# beagle2can.net
KiCad netlist of a schematic drawn in EAGLE
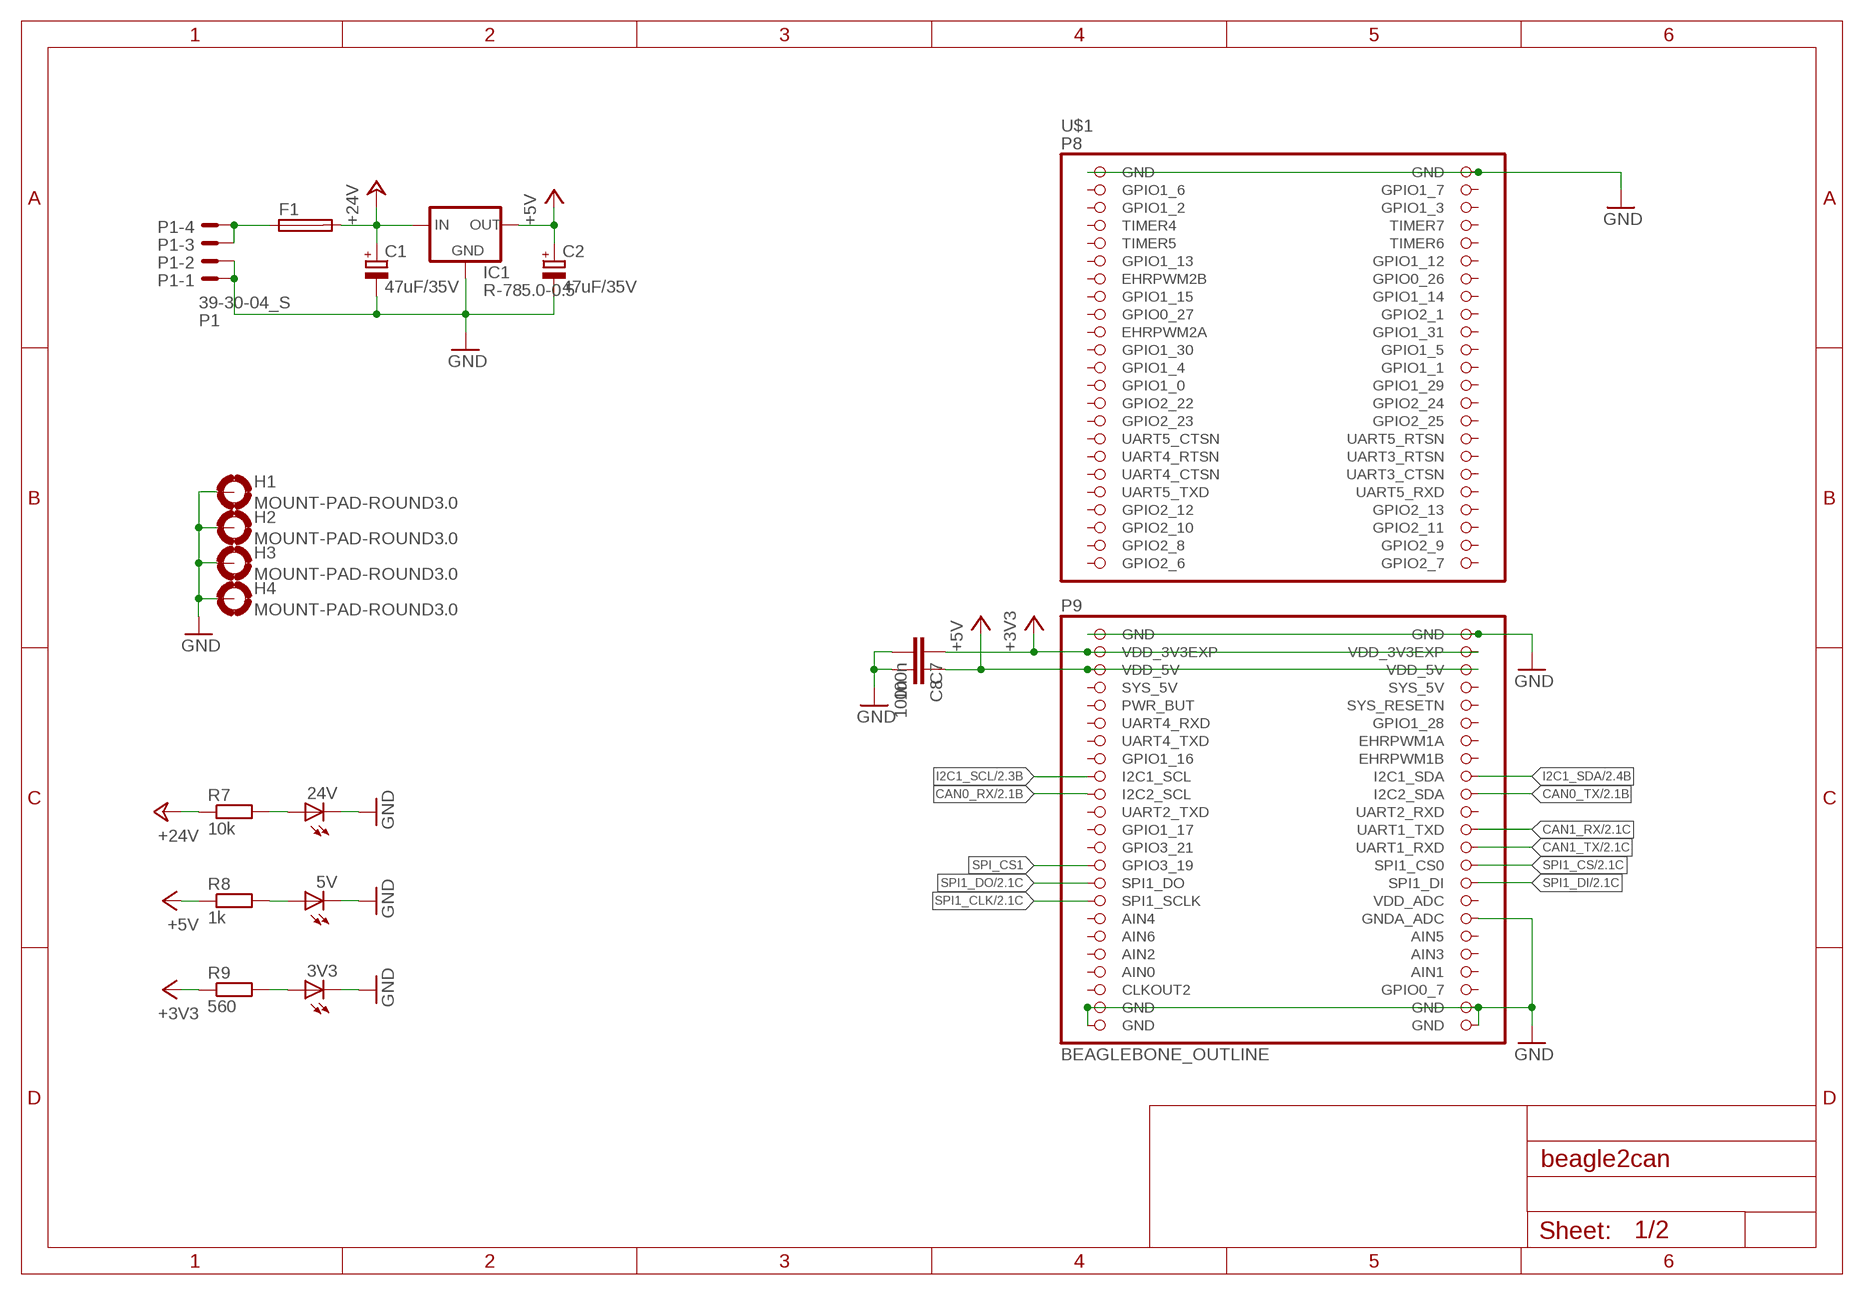
[diagram p0: schematic, sheet 1]
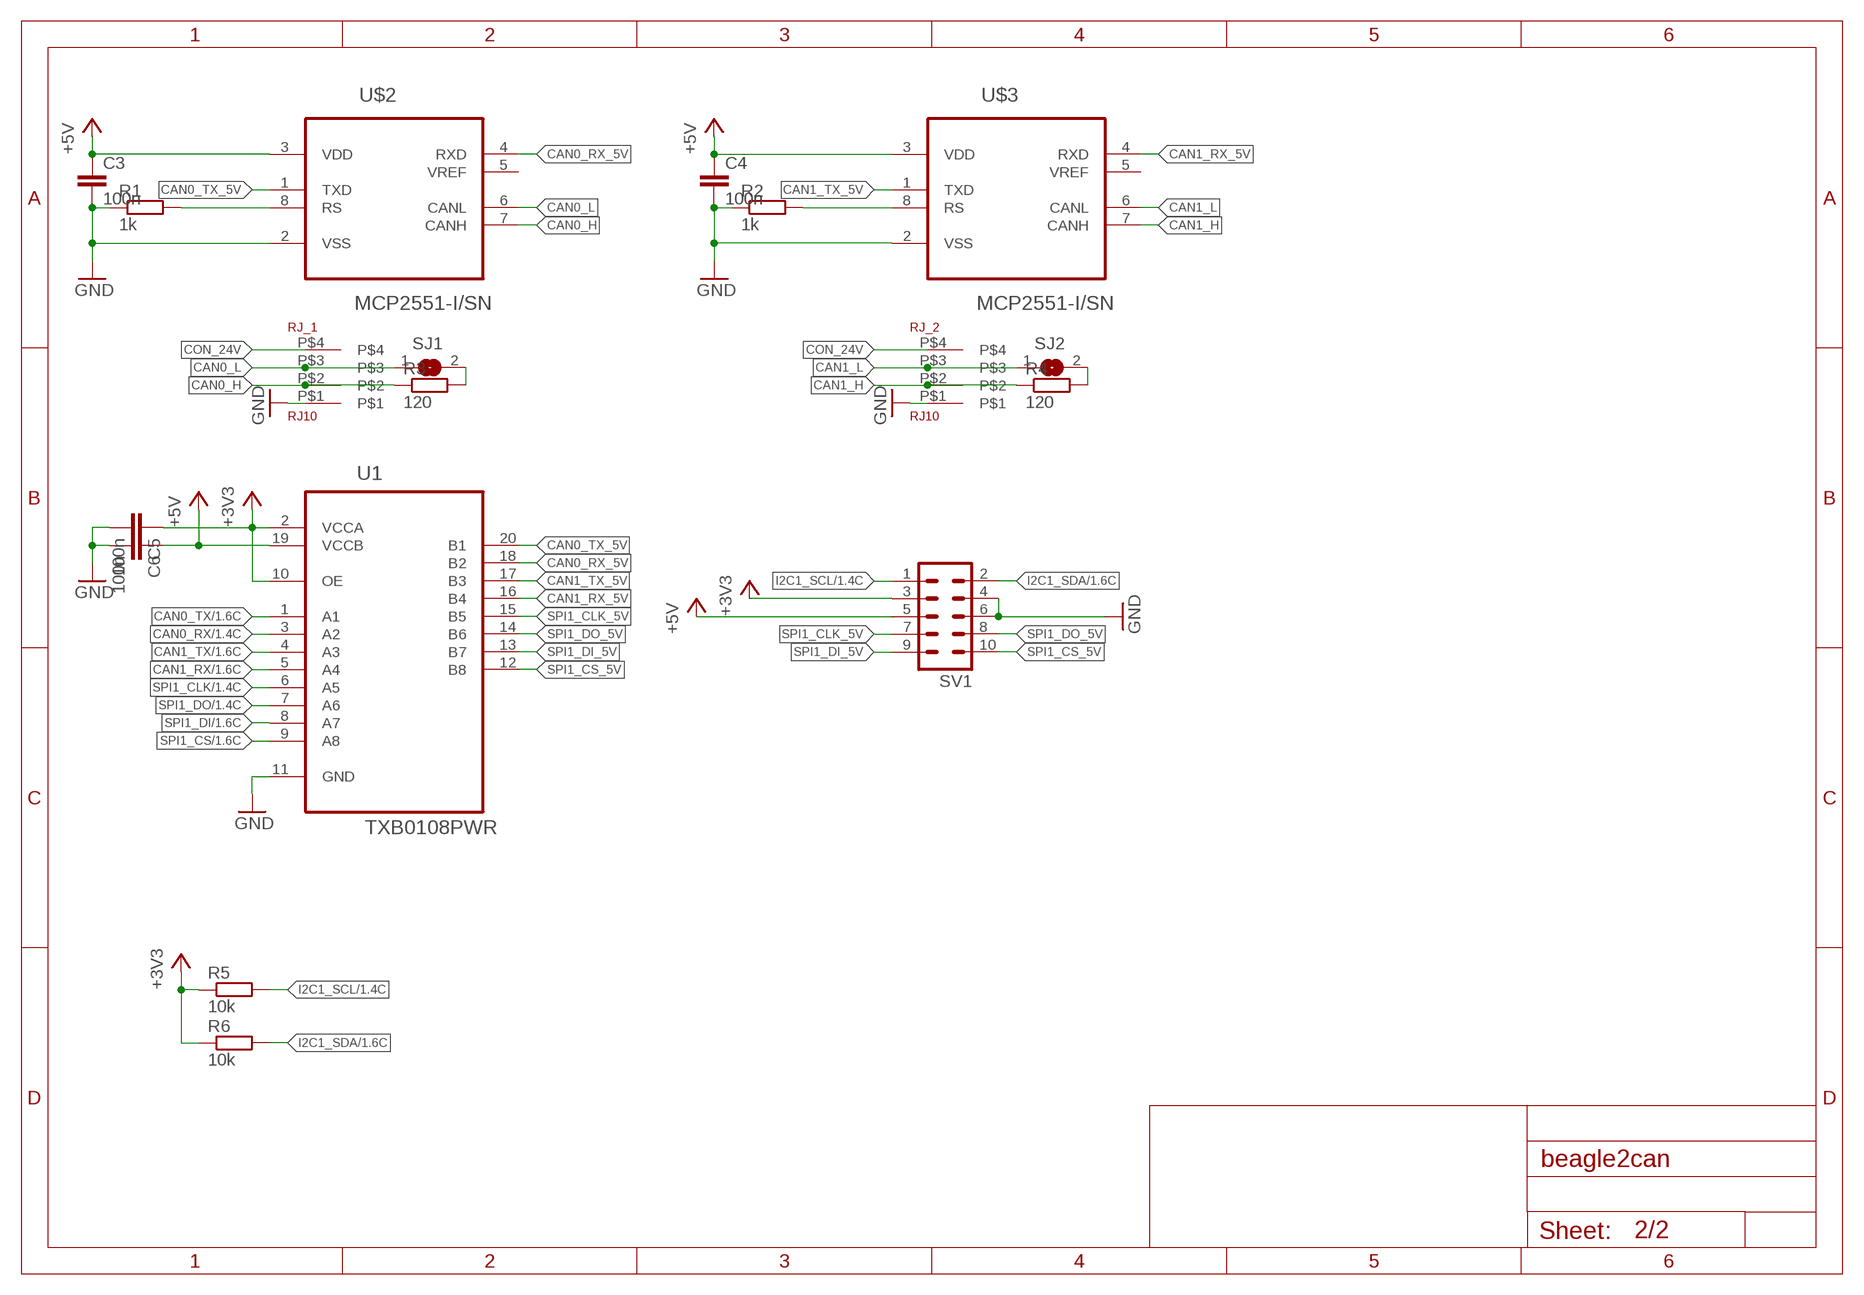
[diagram p1: schematic, sheet 2]

(export (version "E")
  (design (tool "Eeschema 10.0.6"))
  (components
    (comp (ref "C3")
      (value "100n")
      (footprint "eagle-import:C0603")
      (libsource (lib "eagle-import") (part "C-EUC0603"))
    )
    (comp (ref "C4")
      (value "100n")
      (footprint "eagle-import:C0603")
      (libsource (lib "eagle-import") (part "C-EUC0603"))
    )
    (comp (ref "C5")
      (value "100n")
      (footprint "eagle-import:C0603")
      (libsource (lib "eagle-import") (part "C-EUC0603"))
    )
    (comp (ref "C6")
      (value "100n")
      (footprint "eagle-import:C0603")
      (libsource (lib "eagle-import") (part "C-EUC0603"))
    )
    (comp (ref "R1")
      (value "1k")
      (footprint "eagle-import:R0805")
      (libsource (lib "eagle-import") (part "R-EU_R0805"))
    )
    (comp (ref "R2")
      (value "1k")
      (footprint "eagle-import:R0805")
      (libsource (lib "eagle-import") (part "R-EU_R0805"))
    )
    (comp (ref "R3")
      (value "120")
      (footprint "eagle-import:R0805")
      (libsource (lib "eagle-import") (part "R-EU_R0805"))
    )
    (comp (ref "R4")
      (value "120")
      (footprint "eagle-import:R0805")
      (libsource (lib "eagle-import") (part "R-EU_R0805"))
    )
    (comp (ref "R5")
      (value "10k")
      (footprint "eagle-import:R0805")
      (libsource (lib "eagle-import") (part "R-EU_R0805"))
    )
    (comp (ref "R6")
      (value "10k")
      (footprint "eagle-import:R0805")
      (libsource (lib "eagle-import") (part "R-EU_R0805"))
    )
    (comp (ref "RJ_1")
      (value "RJ10")
      (footprint "eagle-import:RJ10")
      (libsource (lib "eagle-import") (part "RJ10"))
    )
    (comp (ref "RJ_2")
      (value "RJ10")
      (footprint "eagle-import:RJ10")
      (libsource (lib "eagle-import") (part "RJ10"))
    )
    (comp (ref "SJ1") (value "SJ") (footprint "eagle-import:SJ") (libsource (lib "eagle-import") (part "SJ")))
    (comp (ref "SJ2") (value "SJ") (footprint "eagle-import:SJ") (libsource (lib "eagle-import") (part "SJ")))
    (comp (ref "SV1")
      (value "ML10L")
      (footprint "eagle-import:ML10L")
      (libsource (lib "eagle-import") (part "ML10L"))
    )
    (comp (ref "U$2")
      (value "MCP2551-I/SN")
      (footprint "eagle-import:SOIC127P600X175-8N")
      (libsource (lib "eagle-import") (part "MCP2551-I/SN"))
    )
    (comp (ref "U$3")
      (value "MCP2551-I/SN")
      (footprint "eagle-import:SOIC127P600X175-8N")
      (libsource (lib "eagle-import") (part "MCP2551-I/SN"))
    )
    (comp (ref "U1")
      (value "TXB0108PWR")
      (footprint "eagle-import:SOP65P640X120-20N")
      (libsource (lib "eagle-import") (part "TXB0108PWR"))
    )
    (comp (ref "3V3")
      (value "LEDCHIP-LED0805")
      (footprint "eagle-import:CHIP-LED0805")
      (libsource (lib "eagle-import") (part "LEDCHIP-LED0805"))
    )
    (comp (ref "5V")
      (value "LEDCHIP-LED0805")
      (footprint "eagle-import:CHIP-LED0805")
      (libsource (lib "eagle-import") (part "LEDCHIP-LED0805"))
    )
    (comp (ref "24V")
      (value "LEDCHIP-LED0805")
      (footprint "eagle-import:CHIP-LED0805")
      (libsource (lib "eagle-import") (part "LEDCHIP-LED0805"))
    )
    (comp (ref "C1")
      (value "47uF/35V")
      (footprint "eagle-import:PANASONIC_D")
      (libsource (lib "eagle-import") (part "CPOL-EUD"))
    )
    (comp (ref "C2")
      (value "47uF/35V")
      (footprint "eagle-import:PANASONIC_D")
      (libsource (lib "eagle-import") (part "CPOL-EUD"))
    )
    (comp (ref "C7")
      (value "100n")
      (footprint "eagle-import:C0603")
      (libsource (lib "eagle-import") (part "C-EUC0603"))
    )
    (comp (ref "C8")
      (value "100n")
      (footprint "eagle-import:C0603")
      (libsource (lib "eagle-import") (part "C-EUC0603"))
    )
    (comp (ref "F1")
      (value "TE5")
      (footprint "eagle-import:TE5")
      (libsource (lib "eagle-import") (part "TE5"))
    )
    (comp (ref "H1")
      (value "MOUNT-PAD-ROUND3.0")
      (footprint "eagle-import:3,0-PAD")
      (libsource (lib "eagle-import") (part "MOUNT-PAD-ROUND3.0"))
    )
    (comp (ref "H2")
      (value "MOUNT-PAD-ROUND3.0")
      (footprint "eagle-import:3,0-PAD")
      (libsource (lib "eagle-import") (part "MOUNT-PAD-ROUND3.0"))
    )
    (comp (ref "H3")
      (value "MOUNT-PAD-ROUND3.0")
      (footprint "eagle-import:3,0-PAD")
      (libsource (lib "eagle-import") (part "MOUNT-PAD-ROUND3.0"))
    )
    (comp (ref "H4")
      (value "MOUNT-PAD-ROUND3.0")
      (footprint "eagle-import:3,0-PAD")
      (libsource (lib "eagle-import") (part "MOUNT-PAD-ROUND3.0"))
    )
    (comp (ref "IC1")
      (value "R-785.0-0.5")
      (footprint "eagle-import:SIP3")
      (fields (field (name "MF") "Recom") (field (name "MPN") "R-785.0-05"))
      (libsource (lib "eagle-import") (part "R-78-0.55.0"))
    )
    (comp (ref "P1")
      (value "39-30-04_S")
      (footprint "eagle-import:39-30-_04_")
      (libsource (lib "eagle-import") (part "39-30-?04?_S"))
    )
    (comp (ref "R7")
      (value "10k")
      (footprint "eagle-import:R0805")
      (libsource (lib "eagle-import") (part "R-EU_R0805"))
    )
    (comp (ref "R8")
      (value "1k")
      (footprint "eagle-import:R0805")
      (libsource (lib "eagle-import") (part "R-EU_R0805"))
    )
    (comp (ref "R9")
      (value "560")
      (footprint "eagle-import:R0805")
      (libsource (lib "eagle-import") (part "R-EU_R0805"))
    )
    (comp (ref "U$1")
      (value "BEAGLEBONE_OUTLINE")
      (footprint "eagle-import:BEAGLEBONE_SHIELD")
      (libsource (lib "eagle-import") (part "BEAGLEBONE_OUTLINE"))
    )
  )
  (nets
    (net (code "1") (name "+3V3") (class "Default")
      (node (ref "C5") (pin "1") (pinfunction "1_1") (pintype "passive"))
      (node (ref "C7") (pin "1") (pinfunction "1_1") (pintype "passive"))
      (node (ref "R5") (pin "1") (pinfunction "1_1") (pintype "passive"))
      (node (ref "R6") (pin "1") (pinfunction "1_1") (pintype "passive"))
      (node (ref "R9") (pin "1") (pinfunction "1_1") (pintype "passive"))
      (node (ref "SV1") (pin "3") (pinfunction "3_3") (pintype "passive"))
      (node (ref "U$1") (pin "49") (pinfunction "VDD_3V3EXP_49") (pintype "power_in"))
      (node (ref "U$1") (pin "50") (pinfunction "VDD_3V3EXP_50") (pintype "power_in"))
      (node (ref "U1") (pin "10") (pinfunction "OE_10") (pintype "input"))
      (node (ref "U1") (pin "2") (pinfunction "VCCA_2") (pintype "power_in"))
    )
    (net (code "2") (name "+5V") (class "Default")
      (node (ref "C2") (pin "+") (pinfunction "+_+") (pintype "passive"))
      (node (ref "C3") (pin "1") (pinfunction "1_1") (pintype "passive"))
      (node (ref "C4") (pin "1") (pinfunction "1_1") (pintype "passive"))
      (node (ref "C6") (pin "1") (pinfunction "1_1") (pintype "passive"))
      (node (ref "C8") (pin "1") (pinfunction "1_1") (pintype "passive"))
      (node (ref "IC1") (pin "3") (pinfunction "OUT_3") (pintype "passive"))
      (node (ref "R8") (pin "1") (pinfunction "1_1") (pintype "passive"))
      (node (ref "SV1") (pin "5") (pinfunction "5_5") (pintype "passive"))
      (node (ref "U$1") (pin "51") (pinfunction "VDD_5V_51") (pintype "power_in"))
      (node (ref "U$1") (pin "52") (pinfunction "VDD_5V_52") (pintype "power_in"))
      (node (ref "U$2") (pin "3") (pinfunction "VDD_3") (pintype "power_in"))
      (node (ref "U$3") (pin "3") (pinfunction "VDD_3") (pintype "power_in"))
      (node (ref "U1") (pin "19") (pinfunction "VCCB_19") (pintype "power_in"))
    )
    (net (code "3") (name "+24V") (class "Default")
      (node (ref "C1") (pin "+") (pinfunction "+_+") (pintype "passive"))
      (node (ref "F1") (pin "2") (pinfunction "2_2") (pintype "passive"))
      (node (ref "IC1") (pin "1") (pinfunction "IN_1") (pintype "input"))
      (node (ref "R7") (pin "1") (pinfunction "1_1") (pintype "passive"))
    )
    (net (code "4") (name "AIN0") (class "Default")
      (node (ref "U$1") (pin "85") (pinfunction "AIN0_85") (pintype "power_in"))
    )
    (net (code "5") (name "CAN0_H") (class "Default")
      (node (ref "R3") (pin "1") (pinfunction "1_1") (pintype "passive"))
      (node (ref "RJ_1") (pin "P$2") (pinfunction "P$2_P$2") (pintype "bidirectional"))
      (node (ref "U$2") (pin "7") (pinfunction "CANH_7") (pintype "bidirectional"))
    )
    (net (code "6") (name "CAN0_L") (class "Default")
      (node (ref "RJ_1") (pin "P$3") (pinfunction "P$3_P$3") (pintype "bidirectional"))
      (node (ref "SJ1") (pin "1") (pinfunction "1_1") (pintype "passive"))
      (node (ref "U$2") (pin "6") (pinfunction "CANL_6") (pintype "bidirectional"))
    )
    (net (code "7") (name "CAN0_RX") (class "Default")
      (node (ref "U$1") (pin "65") (pinfunction "I2C2_SCL_65") (pintype "passive"))
      (node (ref "U1") (pin "3") (pinfunction "A2_3") (pintype "bidirectional"))
    )
    (net (code "8") (name "CAN0_RX_5V") (class "Default")
      (node (ref "U$2") (pin "4") (pinfunction "RXD_4") (pintype "output"))
      (node (ref "U1") (pin "18") (pinfunction "B2_18") (pintype "bidirectional"))
    )
    (net (code "9") (name "CAN0_TX") (class "Default")
      (node (ref "U$1") (pin "66") (pinfunction "I2C2_SDA_66") (pintype "passive"))
      (node (ref "U1") (pin "1") (pinfunction "A1_1") (pintype "bidirectional"))
    )
    (net (code "10") (name "CAN0_TX_5V") (class "Default")
      (node (ref "U$2") (pin "1") (pinfunction "TXD_1") (pintype "input"))
      (node (ref "U1") (pin "20") (pinfunction "B1_20") (pintype "bidirectional"))
    )
    (net (code "11") (name "CAN1_H") (class "Default")
      (node (ref "R4") (pin "1") (pinfunction "1_1") (pintype "passive"))
      (node (ref "RJ_2") (pin "P$2") (pinfunction "P$2_P$2") (pintype "bidirectional"))
      (node (ref "U$3") (pin "7") (pinfunction "CANH_7") (pintype "bidirectional"))
    )
    (net (code "12") (name "CAN1_L") (class "Default")
      (node (ref "RJ_2") (pin "P$3") (pinfunction "P$3_P$3") (pintype "bidirectional"))
      (node (ref "SJ2") (pin "1") (pinfunction "1_1") (pintype "passive"))
      (node (ref "U$3") (pin "6") (pinfunction "CANL_6") (pintype "bidirectional"))
    )
    (net (code "13") (name "CAN1_RX") (class "Default")
      (node (ref "U$1") (pin "70") (pinfunction "UART1_TXD_70") (pintype "passive"))
      (node (ref "U1") (pin "5") (pinfunction "A4_5") (pintype "bidirectional"))
    )
    (net (code "14") (name "CAN1_RX_5V") (class "Default")
      (node (ref "U$3") (pin "4") (pinfunction "RXD_4") (pintype "output"))
      (node (ref "U1") (pin "16") (pinfunction "B4_16") (pintype "bidirectional"))
    )
    (net (code "15") (name "CAN1_TX") (class "Default")
      (node (ref "U$1") (pin "72") (pinfunction "UART1_RXD_72") (pintype "passive"))
      (node (ref "U1") (pin "4") (pinfunction "A3_4") (pintype "bidirectional"))
    )
    (net (code "16") (name "CAN1_TX_5V") (class "Default")
      (node (ref "U$3") (pin "1") (pinfunction "TXD_1") (pintype "input"))
      (node (ref "U1") (pin "17") (pinfunction "B3_17") (pintype "bidirectional"))
    )
    (net (code "17") (name "CON_24V") (class "Default")
      (node (ref "F1") (pin "1") (pinfunction "1_1") (pintype "passive"))
      (node (ref "P1") (pin "3") (pinfunction "P_3") (pintype "passive"))
      (node (ref "P1") (pin "4") (pinfunction "P_4") (pintype "passive"))
      (node (ref "RJ_1") (pin "P$4") (pinfunction "P$4_P$4") (pintype "bidirectional"))
      (node (ref "RJ_2") (pin "P$4") (pinfunction "P$4_P$4") (pintype "bidirectional"))
    )
    (net (code "18") (name "GND") (class "Default")
      (node (ref "24V") (pin "C") (pinfunction "C_C") (pintype "passive"))
      (node (ref "3V3") (pin "C") (pinfunction "C_C") (pintype "passive"))
      (node (ref "5V") (pin "C") (pinfunction "C_C") (pintype "passive"))
      (node (ref "C1") (pin "-") (pinfunction "-_-") (pintype "passive"))
      (node (ref "C2") (pin "-") (pinfunction "-_-") (pintype "passive"))
      (node (ref "C3") (pin "2") (pinfunction "2_2") (pintype "passive"))
      (node (ref "C4") (pin "2") (pinfunction "2_2") (pintype "passive"))
      (node (ref "C5") (pin "2") (pinfunction "2_2") (pintype "passive"))
      (node (ref "C6") (pin "2") (pinfunction "2_2") (pintype "passive"))
      (node (ref "C7") (pin "2") (pinfunction "2_2") (pintype "passive"))
      (node (ref "C8") (pin "2") (pinfunction "2_2") (pintype "passive"))
      (node (ref "H1") (pin "B3,0") (pinfunction "MOUNT_B3,0") (pintype "passive"))
      (node (ref "H2") (pin "B3,0") (pinfunction "MOUNT_B3,0") (pintype "passive"))
      (node (ref "H3") (pin "B3,0") (pinfunction "MOUNT_B3,0") (pintype "passive"))
      (node (ref "H4") (pin "B3,0") (pinfunction "MOUNT_B3,0") (pintype "passive"))
      (node (ref "IC1") (pin "2") (pinfunction "GND_2") (pintype "input"))
      (node (ref "P1") (pin "1") (pinfunction "P_1") (pintype "passive"))
      (node (ref "P1") (pin "2") (pinfunction "P_2") (pintype "passive"))
      (node (ref "R1") (pin "1") (pinfunction "1_1") (pintype "passive"))
      (node (ref "R2") (pin "1") (pinfunction "1_1") (pintype "passive"))
      (node (ref "RJ_1") (pin "P$1") (pinfunction "P$1_P$1") (pintype "bidirectional"))
      (node (ref "RJ_2") (pin "P$1") (pinfunction "P$1_P$1") (pintype "bidirectional"))
      (node (ref "SV1") (pin "4") (pinfunction "4_4") (pintype "passive"))
      (node (ref "SV1") (pin "6") (pinfunction "6_6") (pintype "passive"))
      (node (ref "U$1") (pin "1") (pinfunction "GND_1") (pintype "power_in"))
      (node (ref "U$1") (pin "2") (pinfunction "GND_2") (pintype "power_in"))
      (node (ref "U$1") (pin "47") (pinfunction "GND_47") (pintype "power_in"))
      (node (ref "U$1") (pin "48") (pinfunction "GND_48") (pintype "power_in"))
      (node (ref "U$1") (pin "80") (pinfunction "GNDA_ADC_80") (pintype "passive"))
      (node (ref "U$1") (pin "89") (pinfunction "GND_89") (pintype "power_in"))
      (node (ref "U$1") (pin "90") (pinfunction "GND_90") (pintype "power_in"))
      (node (ref "U$1") (pin "91") (pinfunction "GND_91") (pintype "power_in"))
      (node (ref "U$1") (pin "92") (pinfunction "GND_92") (pintype "power_in"))
      (node (ref "U$2") (pin "2") (pinfunction "VSS_2") (pintype "passive"))
      (node (ref "U$3") (pin "2") (pinfunction "VSS_2") (pintype "passive"))
      (node (ref "U1") (pin "11") (pinfunction "GND_11") (pintype "passive"))
    )
    (net (code "19") (name "I2C1_SCL") (class "Default")
      (node (ref "R5") (pin "2") (pinfunction "2_2") (pintype "passive"))
      (node (ref "SV1") (pin "1") (pinfunction "1_1") (pintype "passive"))
      (node (ref "U$1") (pin "63") (pinfunction "I2C1_SCL_63") (pintype "passive"))
    )
    (net (code "20") (name "I2C1_SDA") (class "Default")
      (node (ref "R6") (pin "2") (pinfunction "2_2") (pintype "passive"))
      (node (ref "SV1") (pin "2") (pinfunction "2_2") (pintype "passive"))
      (node (ref "U$1") (pin "64") (pinfunction "I2C1_SDA_64") (pintype "passive"))
    )
    (net (code "21") (name "Net-(3V3-PadA)") (class "Default")
      (node (ref "3V3") (pin "A") (pinfunction "A_A") (pintype "passive"))
      (node (ref "R9") (pin "2") (pinfunction "2_2") (pintype "passive"))
    )
    (net (code "22") (name "Net-(5V-PadA)") (class "Default")
      (node (ref "5V") (pin "A") (pinfunction "A_A") (pintype "passive"))
      (node (ref "R8") (pin "2") (pinfunction "2_2") (pintype "passive"))
    )
    (net (code "23") (name "Net-(24V-PadA)") (class "Default")
      (node (ref "24V") (pin "A") (pinfunction "A_A") (pintype "passive"))
      (node (ref "R7") (pin "2") (pinfunction "2_2") (pintype "passive"))
    )
    (net (code "24") (name "Net-(R3-Pad2)") (class "Default")
      (node (ref "R3") (pin "2") (pinfunction "2_2") (pintype "passive"))
      (node (ref "SJ1") (pin "2") (pinfunction "2_2") (pintype "passive"))
    )
    (net (code "25") (name "Net-(R4-Pad2)") (class "Default")
      (node (ref "R4") (pin "2") (pinfunction "2_2") (pintype "passive"))
      (node (ref "SJ2") (pin "2") (pinfunction "2_2") (pintype "passive"))
    )
    (net (code "26") (name "Net-(U$2-RS)") (class "Default")
      (node (ref "R1") (pin "2") (pinfunction "2_2") (pintype "passive"))
      (node (ref "U$2") (pin "8") (pinfunction "RS_8") (pintype "input"))
    )
    (net (code "27") (name "Net-(U$3-RS)") (class "Default")
      (node (ref "R2") (pin "2") (pinfunction "2_2") (pintype "passive"))
      (node (ref "U$3") (pin "8") (pinfunction "RS_8") (pintype "input"))
    )
    (net (code "28") (name "SPI1_CLK") (class "Default")
      (node (ref "U$1") (pin "77") (pinfunction "SPI1_SCLK_77") (pintype "passive"))
      (node (ref "U1") (pin "6") (pinfunction "A5_6") (pintype "bidirectional"))
    )
    (net (code "29") (name "SPI1_CLK_5V") (class "Default")
      (node (ref "SV1") (pin "7") (pinfunction "7_7") (pintype "passive"))
      (node (ref "U1") (pin "15") (pinfunction "B5_15") (pintype "bidirectional"))
    )
    (net (code "30") (name "SPI1_CS") (class "Default")
      (node (ref "U$1") (pin "74") (pinfunction "SPI1_CS0_74") (pintype "passive"))
      (node (ref "U1") (pin "9") (pinfunction "A8_9") (pintype "bidirectional"))
    )
    (net (code "31") (name "SPI1_CS_5V") (class "Default")
      (node (ref "SV1") (pin "10") (pinfunction "10_10") (pintype "passive"))
      (node (ref "U1") (pin "12") (pinfunction "B8_12") (pintype "bidirectional"))
    )
    (net (code "32") (name "SPI1_DI") (class "Default")
      (node (ref "U$1") (pin "76") (pinfunction "SPI1_DI_76") (pintype "passive"))
      (node (ref "U1") (pin "8") (pinfunction "A7_8") (pintype "bidirectional"))
    )
    (net (code "33") (name "SPI1_DI_5V") (class "Default")
      (node (ref "SV1") (pin "9") (pinfunction "9_9") (pintype "passive"))
      (node (ref "U1") (pin "13") (pinfunction "B7_13") (pintype "bidirectional"))
    )
    (net (code "34") (name "SPI1_DO") (class "Default")
      (node (ref "U$1") (pin "75") (pinfunction "SPI1_DO_75") (pintype "passive"))
      (node (ref "U1") (pin "7") (pinfunction "A6_7") (pintype "bidirectional"))
    )
    (net (code "35") (name "SPI1_DO_5V") (class "Default")
      (node (ref "SV1") (pin "8") (pinfunction "8_8") (pintype "passive"))
      (node (ref "U1") (pin "14") (pinfunction "B6_14") (pintype "bidirectional"))
    )
    (net (code "36") (name "SPI_CS1") (class "Default")
      (node (ref "U$1") (pin "73") (pinfunction "GPIO3_19_73") (pintype "passive"))
    )
    (net (code "37") (name "SYS_5V") (class "Default")
      (node (ref "U$1") (pin "53") (pinfunction "SYS_5V_53") (pintype "power_in"))
    )
    (net (code "38") (name "unconnected-(U$1-AIN1-Pad86)") (class "Default")
      (node (ref "U$1") (pin "86") (pinfunction "AIN1_86") (pintype "passive"))
    )
    (net (code "39") (name "unconnected-(U$1-AIN2-Pad83)") (class "Default")
      (node (ref "U$1") (pin "83") (pinfunction "AIN2_83") (pintype "passive"))
    )
    (net (code "40") (name "unconnected-(U$1-AIN3-Pad84)") (class "Default")
      (node (ref "U$1") (pin "84") (pinfunction "AIN3_84") (pintype "passive"))
    )
    (net (code "41") (name "unconnected-(U$1-AIN4-Pad79)") (class "Default")
      (node (ref "U$1") (pin "79") (pinfunction "AIN4_79") (pintype "passive"))
    )
    (net (code "42") (name "unconnected-(U$1-AIN5-Pad82)") (class "Default")
      (node (ref "U$1") (pin "82") (pinfunction "AIN5_82") (pintype "passive"))
    )
    (net (code "43") (name "unconnected-(U$1-AIN6-Pad81)") (class "Default")
      (node (ref "U$1") (pin "81") (pinfunction "AIN6_81") (pintype "passive"))
    )
    (net (code "44") (name "unconnected-(U$1-CLKOUT2-Pad87)") (class "Default")
      (node (ref "U$1") (pin "87") (pinfunction "CLKOUT2_87") (pintype "input"))
    )
    (net (code "45") (name "unconnected-(U$1-EHRPWM1A-Pad60)") (class "Default")
      (node (ref "U$1") (pin "60") (pinfunction "EHRPWM1A_60") (pintype "passive"))
    )
    (net (code "46") (name "unconnected-(U$1-EHRPWM1B-Pad62)") (class "Default")
      (node (ref "U$1") (pin "62") (pinfunction "EHRPWM1B_62") (pintype "passive"))
    )
    (net (code "47") (name "unconnected-(U$1-EHRPWM2A-Pad19)") (class "Default")
      (node (ref "U$1") (pin "19") (pinfunction "EHRPWM2A_19") (pintype "passive"))
    )
    (net (code "48") (name "unconnected-(U$1-EHRPWM2B-Pad13)") (class "Default")
      (node (ref "U$1") (pin "13") (pinfunction "EHRPWM2B_13") (pintype "passive"))
    )
    (net (code "49") (name "unconnected-(U$1-GPIO0_7-Pad88)") (class "Default")
      (node (ref "U$1") (pin "88") (pinfunction "GPIO0_7_88") (pintype "passive"))
    )
    (net (code "50") (name "unconnected-(U$1-GPIO0_26-Pad14)") (class "Default")
      (node (ref "U$1") (pin "14") (pinfunction "GPIO0_26_14") (pintype "passive"))
    )
    (net (code "51") (name "unconnected-(U$1-GPIO0_27-Pad17)") (class "Default")
      (node (ref "U$1") (pin "17") (pinfunction "GPIO0_27_17") (pintype "passive"))
    )
    (net (code "52") (name "unconnected-(U$1-GPIO1_0-Pad25)") (class "Default")
      (node (ref "U$1") (pin "25") (pinfunction "GPIO1_0_25") (pintype "passive"))
    )
    (net (code "53") (name "unconnected-(U$1-GPIO1_1-Pad24)") (class "Default")
      (node (ref "U$1") (pin "24") (pinfunction "GPIO1_1_24") (pintype "passive"))
    )
    (net (code "54") (name "unconnected-(U$1-GPIO1_2-Pad5)") (class "Default")
      (node (ref "U$1") (pin "5") (pinfunction "GPIO1_2_5") (pintype "passive"))
    )
    (net (code "55") (name "unconnected-(U$1-GPIO1_3-Pad6)") (class "Default")
      (node (ref "U$1") (pin "6") (pinfunction "GPIO1_3_6") (pintype "passive"))
    )
    (net (code "56") (name "unconnected-(U$1-GPIO1_4-Pad23)") (class "Default")
      (node (ref "U$1") (pin "23") (pinfunction "GPIO1_4_23") (pintype "passive"))
    )
    (net (code "57") (name "unconnected-(U$1-GPIO1_5-Pad22)") (class "Default")
      (node (ref "U$1") (pin "22") (pinfunction "GPIO1_5_22") (pintype "passive"))
    )
    (net (code "58") (name "unconnected-(U$1-GPIO1_6-Pad3)") (class "Default")
      (node (ref "U$1") (pin "3") (pinfunction "GPIO1_6_3") (pintype "passive"))
    )
    (net (code "59") (name "unconnected-(U$1-GPIO1_7-Pad4)") (class "Default")
      (node (ref "U$1") (pin "4") (pinfunction "GPIO1_7_4") (pintype "passive"))
    )
    (net (code "60") (name "unconnected-(U$1-GPIO1_12-Pad12)") (class "Default")
      (node (ref "U$1") (pin "12") (pinfunction "GPIO1_12_12") (pintype "passive"))
    )
    (net (code "61") (name "unconnected-(U$1-GPIO1_13-Pad11)") (class "Default")
      (node (ref "U$1") (pin "11") (pinfunction "GPIO1_13_11") (pintype "passive"))
    )
    (net (code "62") (name "unconnected-(U$1-GPIO1_14-Pad16)") (class "Default")
      (node (ref "U$1") (pin "16") (pinfunction "GPIO1_14_16") (pintype "passive"))
    )
    (net (code "63") (name "unconnected-(U$1-GPIO1_15-Pad15)") (class "Default")
      (node (ref "U$1") (pin "15") (pinfunction "GPIO1_15_15") (pintype "passive"))
    )
    (net (code "64") (name "unconnected-(U$1-GPIO1_16-Pad61)") (class "Default")
      (node (ref "U$1") (pin "61") (pinfunction "GPIO1_16_61") (pintype "passive"))
    )
    (net (code "65") (name "unconnected-(U$1-GPIO1_17-Pad69)") (class "Default")
      (node (ref "U$1") (pin "69") (pinfunction "GPIO1_17_69") (pintype "passive"))
    )
    (net (code "66") (name "unconnected-(U$1-GPIO1_28-Pad58)") (class "Default")
      (node (ref "U$1") (pin "58") (pinfunction "GPIO1_28_58") (pintype "passive"))
    )
    (net (code "67") (name "unconnected-(U$1-GPIO1_29-Pad26)") (class "Default")
      (node (ref "U$1") (pin "26") (pinfunction "GPIO1_29_26") (pintype "passive"))
    )
    (net (code "68") (name "unconnected-(U$1-GPIO1_30-Pad21)") (class "Default")
      (node (ref "U$1") (pin "21") (pinfunction "GPIO1_30_21") (pintype "passive"))
    )
    (net (code "69") (name "unconnected-(U$1-GPIO1_31-Pad20)") (class "Default")
      (node (ref "U$1") (pin "20") (pinfunction "GPIO1_31_20") (pintype "passive"))
    )
    (net (code "70") (name "unconnected-(U$1-GPIO2_1-Pad18)") (class "Default")
      (node (ref "U$1") (pin "18") (pinfunction "GPIO2_1_18") (pintype "passive"))
    )
    (net (code "71") (name "unconnected-(U$1-GPIO2_6-Pad45)") (class "Default")
      (node (ref "U$1") (pin "45") (pinfunction "GPIO2_6_45") (pintype "passive"))
    )
    (net (code "72") (name "unconnected-(U$1-GPIO2_7-Pad46)") (class "Default")
      (node (ref "U$1") (pin "46") (pinfunction "GPIO2_7_46") (pintype "passive"))
    )
    (net (code "73") (name "unconnected-(U$1-GPIO2_8-Pad43)") (class "Default")
      (node (ref "U$1") (pin "43") (pinfunction "GPIO2_8_43") (pintype "passive"))
    )
    (net (code "74") (name "unconnected-(U$1-GPIO2_9-Pad44)") (class "Default")
      (node (ref "U$1") (pin "44") (pinfunction "GPIO2_9_44") (pintype "passive"))
    )
    (net (code "75") (name "unconnected-(U$1-GPIO2_10-Pad41)") (class "Default")
      (node (ref "U$1") (pin "41") (pinfunction "GPIO2_10_41") (pintype "passive"))
    )
    (net (code "76") (name "unconnected-(U$1-GPIO2_11-Pad42)") (class "Default")
      (node (ref "U$1") (pin "42") (pinfunction "GPIO2_11_42") (pintype "passive"))
    )
    (net (code "77") (name "unconnected-(U$1-GPIO2_12-Pad39)") (class "Default")
      (node (ref "U$1") (pin "39") (pinfunction "GPIO2_12_39") (pintype "passive"))
    )
    (net (code "78") (name "unconnected-(U$1-GPIO2_13-Pad40)") (class "Default")
      (node (ref "U$1") (pin "40") (pinfunction "GPIO2_13_40") (pintype "passive"))
    )
    (net (code "79") (name "unconnected-(U$1-GPIO2_22-Pad27)") (class "Default")
      (node (ref "U$1") (pin "27") (pinfunction "GPIO2_22_27") (pintype "passive"))
    )
    (net (code "80") (name "unconnected-(U$1-GPIO2_23-Pad29)") (class "Default")
      (node (ref "U$1") (pin "29") (pinfunction "GPIO2_23_29") (pintype "passive"))
    )
    (net (code "81") (name "unconnected-(U$1-GPIO2_24-Pad28)") (class "Default")
      (node (ref "U$1") (pin "28") (pinfunction "GPIO2_24_28") (pintype "passive"))
    )
    (net (code "82") (name "unconnected-(U$1-GPIO2_25-Pad30)") (class "Default")
      (node (ref "U$1") (pin "30") (pinfunction "GPIO2_25_30") (pintype "passive"))
    )
    (net (code "83") (name "unconnected-(U$1-GPIO3_21-Pad71)") (class "Default")
      (node (ref "U$1") (pin "71") (pinfunction "GPIO3_21_71") (pintype "passive"))
    )
    (net (code "84") (name "unconnected-(U$1-PWR_BUT-Pad55)") (class "Default")
      (node (ref "U$1") (pin "55") (pinfunction "PWR_BUT_55") (pintype "passive"))
    )
    (net (code "85") (name "unconnected-(U$1-SYS_5V-Pad54)") (class "Default")
      (node (ref "U$1") (pin "54") (pinfunction "SYS_5V_54") (pintype "passive"))
    )
    (net (code "86") (name "unconnected-(U$1-SYS_RESETN-Pad56)") (class "Default")
      (node (ref "U$1") (pin "56") (pinfunction "SYS_RESETN_56") (pintype "passive"))
    )
    (net (code "87") (name "unconnected-(U$1-TIMER4-Pad7)") (class "Default")
      (node (ref "U$1") (pin "7") (pinfunction "TIMER4_7") (pintype "passive"))
    )
    (net (code "88") (name "unconnected-(U$1-TIMER5-Pad9)") (class "Default")
      (node (ref "U$1") (pin "9") (pinfunction "TIMER5_9") (pintype "passive"))
    )
    (net (code "89") (name "unconnected-(U$1-TIMER6-Pad10)") (class "Default")
      (node (ref "U$1") (pin "10") (pinfunction "TIMER6_10") (pintype "passive"))
    )
    (net (code "90") (name "unconnected-(U$1-TIMER7-Pad8)") (class "Default")
      (node (ref "U$1") (pin "8") (pinfunction "TIMER7_8") (pintype "passive"))
    )
    (net (code "91") (name "unconnected-(U$1-UART2_RXD-Pad68)") (class "Default")
      (node (ref "U$1") (pin "68") (pinfunction "UART2_RXD_68") (pintype "passive"))
    )
    (net (code "92") (name "unconnected-(U$1-UART2_TXD-Pad67)") (class "Default")
      (node (ref "U$1") (pin "67") (pinfunction "UART2_TXD_67") (pintype "passive"))
    )
    (net (code "93") (name "unconnected-(U$1-UART3_CTSN-Pad36)") (class "Default")
      (node (ref "U$1") (pin "36") (pinfunction "UART3_CTSN_36") (pintype "passive"))
    )
    (net (code "94") (name "unconnected-(U$1-UART3_RTSN-Pad34)") (class "Default")
      (node (ref "U$1") (pin "34") (pinfunction "UART3_RTSN_34") (pintype "passive"))
    )
    (net (code "95") (name "unconnected-(U$1-UART4_CTSN-Pad35)") (class "Default")
      (node (ref "U$1") (pin "35") (pinfunction "UART4_CTSN_35") (pintype "passive"))
    )
    (net (code "96") (name "unconnected-(U$1-UART4_RTSN-Pad33)") (class "Default")
      (node (ref "U$1") (pin "33") (pinfunction "UART4_RTSN_33") (pintype "passive"))
    )
    (net (code "97") (name "unconnected-(U$1-UART4_RXD-Pad57)") (class "Default")
      (node (ref "U$1") (pin "57") (pinfunction "UART4_RXD_57") (pintype "passive"))
    )
    (net (code "98") (name "unconnected-(U$1-UART4_TXD-Pad59)") (class "Default")
      (node (ref "U$1") (pin "59") (pinfunction "UART4_TXD_59") (pintype "passive"))
    )
    (net (code "99") (name "unconnected-(U$1-UART5_CTSN-Pad31)") (class "Default")
      (node (ref "U$1") (pin "31") (pinfunction "UART5_CTSN_31") (pintype "passive"))
    )
    (net (code "100") (name "unconnected-(U$1-UART5_RTSN-Pad32)") (class "Default")
      (node (ref "U$1") (pin "32") (pinfunction "UART5_RTSN_32") (pintype "passive"))
    )
    (net (code "101") (name "unconnected-(U$1-UART5_RXD-Pad38)") (class "Default")
      (node (ref "U$1") (pin "38") (pinfunction "UART5_RXD_38") (pintype "passive"))
    )
    (net (code "102") (name "unconnected-(U$1-UART5_TXD-Pad37)") (class "Default")
      (node (ref "U$1") (pin "37") (pinfunction "UART5_TXD_37") (pintype "passive"))
    )
    (net (code "103") (name "unconnected-(U$1-VDD_ADC-Pad78)") (class "Default")
      (node (ref "U$1") (pin "78") (pinfunction "VDD_ADC_78") (pintype "passive"))
    )
    (net (code "104") (name "unconnected-(U$2-VREF-Pad5)") (class "Default")
      (node (ref "U$2") (pin "5") (pinfunction "VREF_5") (pintype "output"))
    )
    (net (code "105") (name "unconnected-(U$3-VREF-Pad5)") (class "Default")
      (node (ref "U$3") (pin "5") (pinfunction "VREF_5") (pintype "output"))
    )
  )
)
